# s-ispv2_1.net
KiCad netlist of a schematic drawn in EAGLE
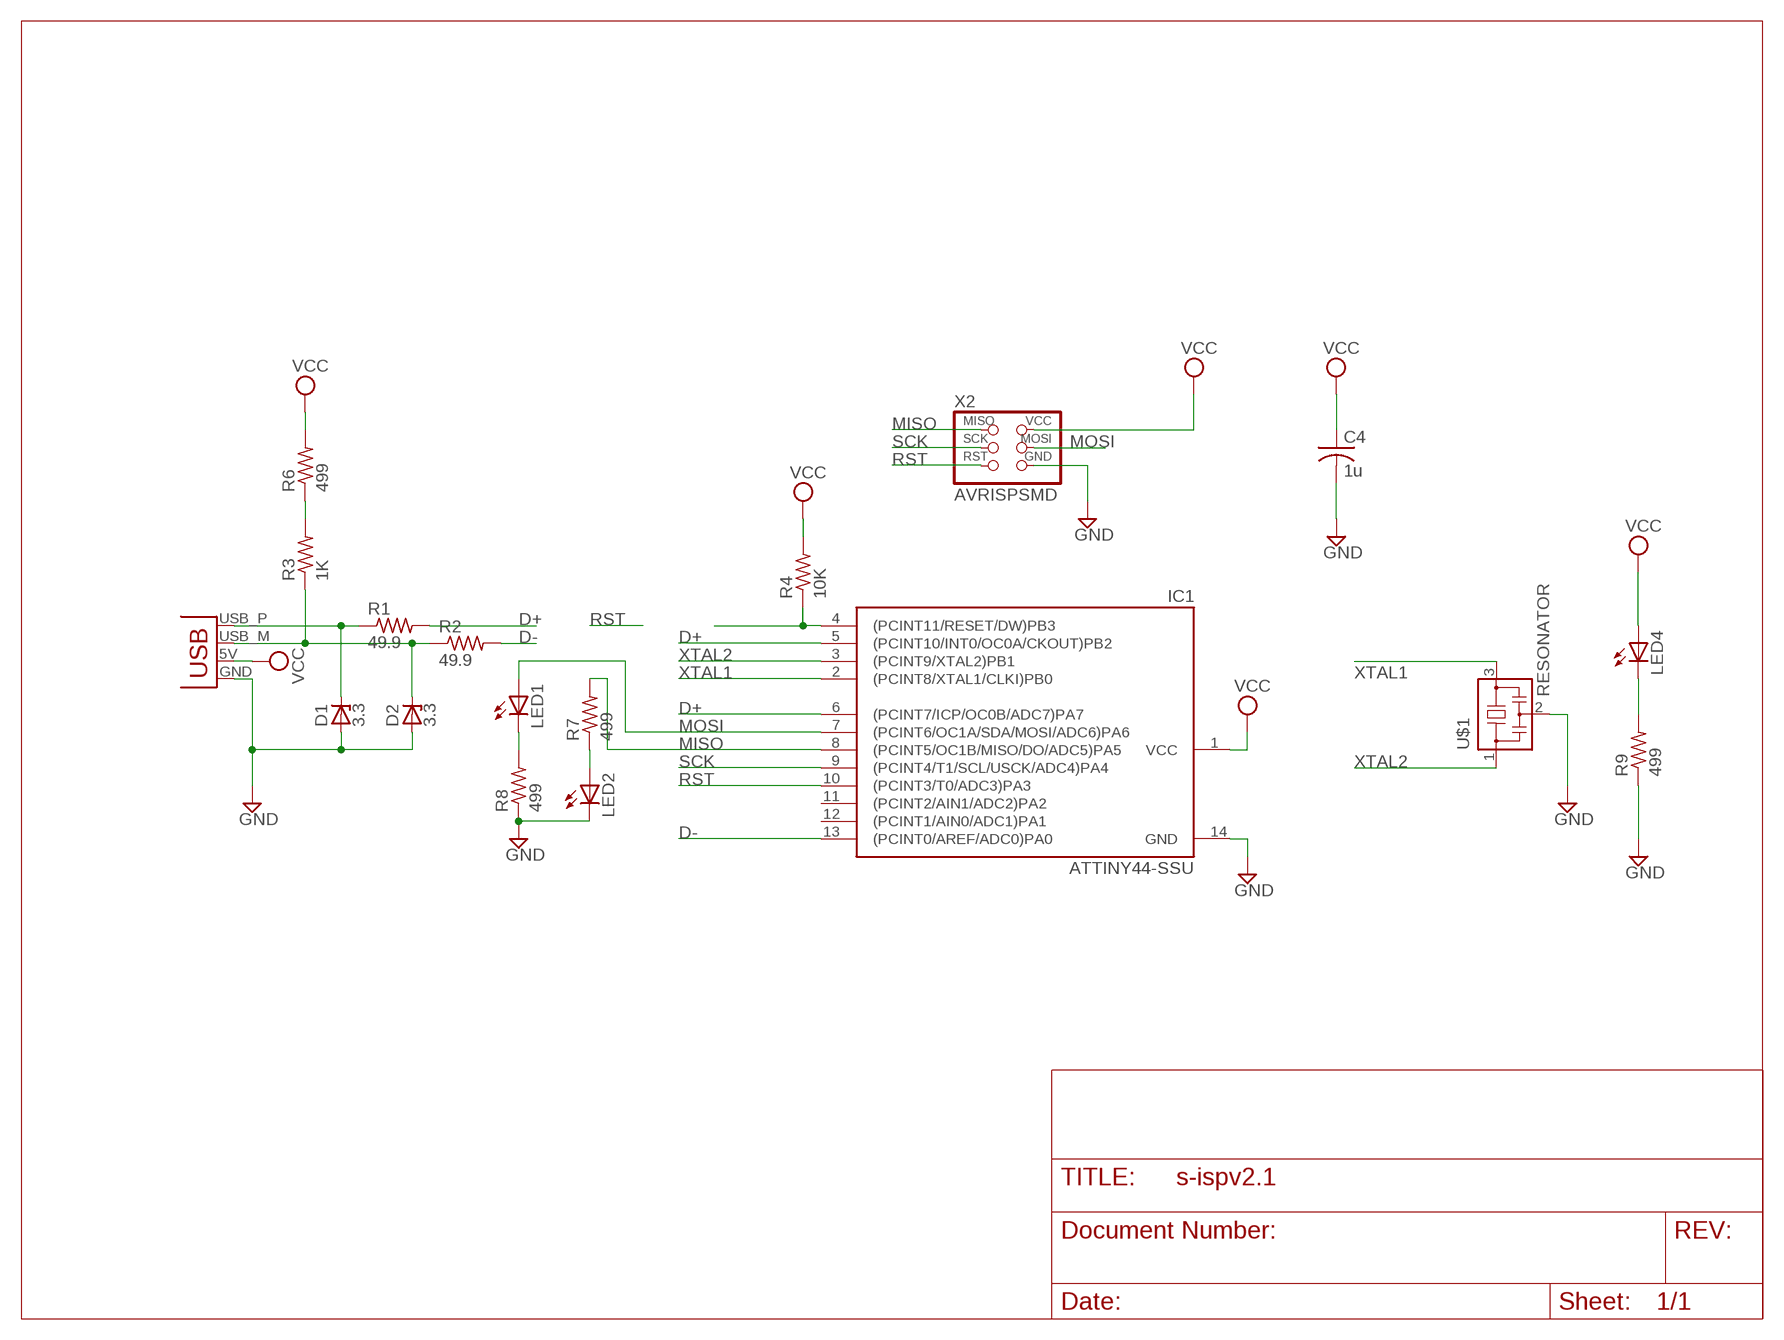
[diagram p0: schematic, sheet 1]

(export (version "E")
  (design (tool "Eeschema 10.0.6"))
  (components
    (comp (ref "C4")
      (value "1u")
      (footprint "eagle-import:C1206")
      (libsource (lib "eagle-import") (part "C-USC1206"))
    )
    (comp (ref "D1")
      (value "3.3")
      (footprint "eagle-import:SOD123")
      (libsource (lib "eagle-import") (part "ZENER_DIODESOD123"))
    )
    (comp (ref "D2")
      (value "3.3")
      (footprint "eagle-import:SOD123")
      (libsource (lib "eagle-import") (part "ZENER_DIODESOD123"))
    )
    (comp (ref "IC1")
      (value "ATTINY44-SSU")
      (footprint "eagle-import:SOIC14")
      (libsource (lib "eagle-import") (part "ATTINY44-SSU"))
    )
    (comp (ref "LED1")
      (value "LEDSMT1206")
      (footprint "eagle-import:1206")
      (libsource (lib "eagle-import") (part "LEDSMT1206"))
    )
    (comp (ref "LED2")
      (value "LEDSMT1206")
      (footprint "eagle-import:1206")
      (libsource (lib "eagle-import") (part "LEDSMT1206"))
    )
    (comp (ref "LED4")
      (value "LEDSMT1206")
      (footprint "eagle-import:1206")
      (libsource (lib "eagle-import") (part "LEDSMT1206"))
    )
    (comp (ref "R1")
      (value "49.9")
      (footprint "eagle-import:R1206")
      (libsource (lib "eagle-import") (part "R-US_R1206"))
    )
    (comp (ref "R2")
      (value "49.9")
      (footprint "eagle-import:R1206")
      (libsource (lib "eagle-import") (part "R-US_R1206"))
    )
    (comp (ref "R3")
      (value "1K")
      (footprint "eagle-import:R1206")
      (libsource (lib "eagle-import") (part "R-US_R1206"))
    )
    (comp (ref "R4")
      (value "10K")
      (footprint "eagle-import:R1206")
      (libsource (lib "eagle-import") (part "R-US_R1206"))
    )
    (comp (ref "R6")
      (value "499")
      (footprint "eagle-import:R1206")
      (libsource (lib "eagle-import") (part "R-US_R1206"))
    )
    (comp (ref "R7")
      (value "499")
      (footprint "eagle-import:R1206")
      (libsource (lib "eagle-import") (part "R-US_R1206"))
    )
    (comp (ref "R8")
      (value "499")
      (footprint "eagle-import:R1206")
      (libsource (lib "eagle-import") (part "R-US_R1206"))
    )
    (comp (ref "R9")
      (value "499")
      (footprint "eagle-import:R1206")
      (libsource (lib "eagle-import") (part "R-US_R1206"))
    )
    (comp (ref "U$1")
      (value "RESONATOR")
      (footprint "eagle-import:EFOBM")
      (libsource (lib "eagle-import") (part "RESONATOR"))
    )
    (comp (ref "X1")
      (value "USBPCB")
      (footprint "eagle-import:USB-A-PCB")
      (libsource (lib "eagle-import") (part "USBPCB"))
    )
    (comp (ref "X2")
      (value "AVRISPSMD")
      (footprint "eagle-import:2X03SMD")
      (libsource (lib "eagle-import") (part "AVRISPSMD"))
    )
  )
  (nets
    (net (code "1") (name "/D+") (class "Default")
      (node (ref "IC1") (pin "5") (pinfunction "(PCINT10/INT0/OC0A/CKOUT)PB2_5") (pintype "bidirectional"))
      (node (ref "IC1") (pin "6") (pinfunction "(PCINT7/ICP/OC0B/ADC7)PA7_6") (pintype "bidirectional"))
      (node (ref "R1") (pin "2") (pinfunction "2_2") (pintype "passive"))
    )
    (net (code "2") (name "/D-") (class "Default")
      (node (ref "IC1") (pin "13") (pinfunction "(PCINT0/AREF/ADC0)PA0_13") (pintype "bidirectional"))
      (node (ref "R2") (pin "2") (pinfunction "2_2") (pintype "passive"))
    )
    (net (code "3") (name "/MISO") (class "Default")
      (node (ref "IC1") (pin "8") (pinfunction "(PCINT5/OC1B/MISO/DO/ADC5)PA5_8") (pintype "bidirectional"))
      (node (ref "R7") (pin "2") (pinfunction "2_2") (pintype "passive"))
      (node (ref "X2") (pin "1") (pinfunction "MISO_1") (pintype "passive"))
    )
    (net (code "4") (name "/MOSI") (class "Default")
      (node (ref "IC1") (pin "7") (pinfunction "(PCINT6/OC1A/SDA/MOSI/ADC6)PA6_7") (pintype "bidirectional"))
      (node (ref "LED1") (pin "A") (pinfunction "A_A") (pintype "passive"))
      (node (ref "X2") (pin "4") (pinfunction "MOSI_4") (pintype "passive"))
    )
    (net (code "5") (name "/RST") (class "Default")
      (node (ref "IC1") (pin "10") (pinfunction "(PCINT3/T0/ADC3)PA3_10") (pintype "bidirectional"))
      (node (ref "IC1") (pin "4") (pinfunction "(PCINT11/RESET/DW)PB3_4") (pintype "bidirectional"))
      (node (ref "R4") (pin "1") (pinfunction "1_1") (pintype "passive"))
      (node (ref "X2") (pin "5") (pinfunction "RST_5") (pintype "passive"))
    )
    (net (code "6") (name "/SCK") (class "Default")
      (node (ref "IC1") (pin "9") (pinfunction "(PCINT4/T1/SCL/USCK/ADC4)PA4_9") (pintype "bidirectional"))
      (node (ref "X2") (pin "3") (pinfunction "SCK_3") (pintype "passive"))
    )
    (net (code "7") (name "/XTAL1") (class "Default")
      (node (ref "IC1") (pin "2") (pinfunction "(PCINT8/XTAL1/CLKI)PB0_2") (pintype "bidirectional"))
      (node (ref "U$1") (pin "3") (pinfunction "3_3") (pintype "passive"))
    )
    (net (code "8") (name "/XTAL2") (class "Default")
      (node (ref "IC1") (pin "3") (pinfunction "(PCINT9/XTAL2)PB1_3") (pintype "bidirectional"))
      (node (ref "U$1") (pin "1") (pinfunction "1_1") (pintype "passive"))
    )
    (net (code "9") (name "GND") (class "Default")
      (node (ref "C4") (pin "2") (pinfunction "2_2") (pintype "passive"))
      (node (ref "D1") (pin "ANODE") (pinfunction "ANODE_ANODE") (pintype "passive"))
      (node (ref "D2") (pin "ANODE") (pinfunction "ANODE_ANODE") (pintype "passive"))
      (node (ref "IC1") (pin "14") (pinfunction "GND_14") (pintype "power_in"))
      (node (ref "LED2") (pin "C") (pinfunction "C_C") (pintype "passive"))
      (node (ref "R8") (pin "1") (pinfunction "1_1") (pintype "passive"))
      (node (ref "R9") (pin "1") (pinfunction "1_1") (pintype "passive"))
      (node (ref "U$1") (pin "2") (pinfunction "2_2") (pintype "passive"))
      (node (ref "X1") (pin "GND") (pinfunction "GND_GND") (pintype "bidirectional"))
      (node (ref "X2") (pin "6") (pinfunction "GND_6") (pintype "passive"))
    )
    (net (code "10") (name "Net-(LED1-PadC)") (class "Default")
      (node (ref "LED1") (pin "C") (pinfunction "C_C") (pintype "passive"))
      (node (ref "R8") (pin "2") (pinfunction "2_2") (pintype "passive"))
    )
    (net (code "11") (name "Net-(LED2-PadA)") (class "Default")
      (node (ref "LED2") (pin "A") (pinfunction "A_A") (pintype "passive"))
      (node (ref "R7") (pin "1") (pinfunction "1_1") (pintype "passive"))
    )
    (net (code "12") (name "Net-(LED4-PadC)") (class "Default")
      (node (ref "LED4") (pin "C") (pinfunction "C_C") (pintype "passive"))
      (node (ref "R9") (pin "2") (pinfunction "2_2") (pintype "passive"))
    )
    (net (code "13") (name "Net-(R3-Pad2)") (class "Default")
      (node (ref "R3") (pin "2") (pinfunction "2_2") (pintype "passive"))
      (node (ref "R6") (pin "1") (pinfunction "1_1") (pintype "passive"))
    )
    (net (code "14") (name "Net-(X1-D+)") (class "Default")
      (node (ref "D1") (pin "CATHODE") (pinfunction "CATHODE_CATHODE") (pintype "passive"))
      (node (ref "R1") (pin "1") (pinfunction "1_1") (pintype "passive"))
      (node (ref "X1") (pin "USB_P") (pinfunction "D+_USB_P") (pintype "bidirectional"))
    )
    (net (code "15") (name "Net-(X1-D-)") (class "Default")
      (node (ref "D2") (pin "CATHODE") (pinfunction "CATHODE_CATHODE") (pintype "passive"))
      (node (ref "R2") (pin "1") (pinfunction "1_1") (pintype "passive"))
      (node (ref "R3") (pin "1") (pinfunction "1_1") (pintype "passive"))
      (node (ref "X1") (pin "USB_M") (pinfunction "D-_USB_M") (pintype "bidirectional"))
    )
    (net (code "16") (name "VCC") (class "Default")
      (node (ref "C4") (pin "1") (pinfunction "1_1") (pintype "passive"))
      (node (ref "IC1") (pin "1") (pinfunction "VCC_1") (pintype "power_in"))
      (node (ref "LED4") (pin "A") (pinfunction "A_A") (pintype "passive"))
      (node (ref "R4") (pin "2") (pinfunction "2_2") (pintype "passive"))
      (node (ref "R6") (pin "2") (pinfunction "2_2") (pintype "passive"))
      (node (ref "X1") (pin "5V") (pinfunction "VBUS_5V") (pintype "bidirectional"))
      (node (ref "X2") (pin "2") (pinfunction "VCC_2") (pintype "passive"))
    )
    (net (code "17") (name "unconnected-(IC1-(PCINT1{slash}AIN0{slash}ADC1)PA1-Pad12)") (class "Default")
      (node (ref "IC1") (pin "12") (pinfunction "(PCINT1/AIN0/ADC1)PA1_12") (pintype "bidirectional"))
    )
    (net (code "18") (name "unconnected-(IC1-(PCINT2{slash}AIN1{slash}ADC2)PA2-Pad11)") (class "Default")
      (node (ref "IC1") (pin "11") (pinfunction "(PCINT2/AIN1/ADC2)PA2_11") (pintype "bidirectional"))
    )
  )
)
